# powerPCB9-2.net
KiCad netlist of a schematic drawn in Altium Designer
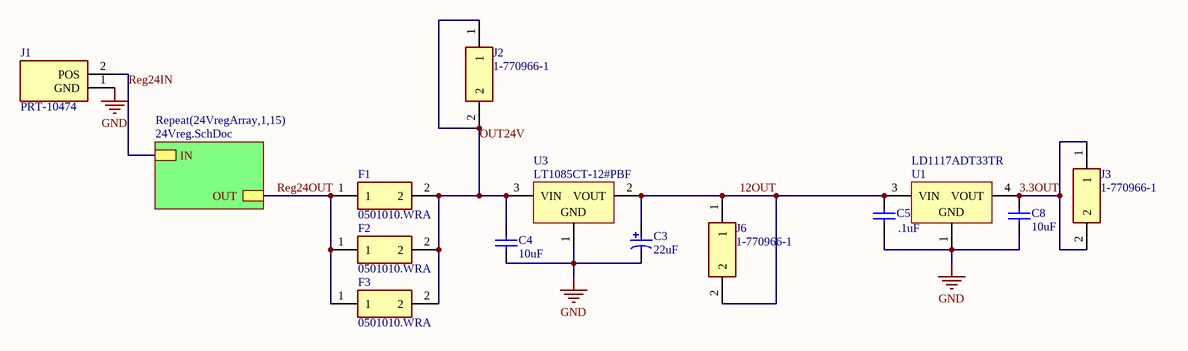
[diagram p0: powerPCB9-2.SchDoc]

(export (version "E")
  (design (tool "Eeschema 10.0.6"))
  (components
    (comp (ref "C3")
      (value "22uF")
      (footprint "KEMT-D-7343-31-2_L")
      (description "Capacitor, Tantalum, 22 uF, +/- 10%, 35 V, -55 to 125 degC, 2-Pin Molded, RoHS, Tape and Reel")
      (fields (field (name "VOLTAGE") "35VDC") (field (name "MANUFACTURER") "Kemet"))
      (libsource (lib "Altium Content Vault") (part "CAP-P-2"))
    )
    (comp (ref "C4")
      (value "10uF")
      (footprint "CAPC2013X135X45ML10T25")
      (fields (field (name "PART NUMBER") "GRM21BR61E106KA73L") (field (name "MANUFACTURER") "Murata"))
      (libsource (lib "Altium Content Vault") (part "CAP"))
    )
    (comp (ref "C5")
      (value ".1uF")
      (footprint "CAPC2013X135X45ML10T25")
      (description "Chip Capacitor, 0.1 uF, +/- 10%, 50 V, -55 to 125 degC, 0805 (2012 Metric), RoHS, Tape and Reel")
      (fields (field (name "VOLTAGE") "50V") (field (name "TOLERANCE") "10%"))
      (libsource (lib "Altium Content Vault") (part "CAP-NP-2"))
    )
    (comp (ref "C8")
      (value "10uF")
      (footprint "CAPC2013X135X45ML10T25")
      (fields (field (name "PART NUMBER") "GRM21BR61E106KA73L") (field (name "MANUFACTURER") "Murata"))
      (libsource (lib "Altium Content Vault") (part "CAP"))
    )
    (comp (ref "F1")
      (value "0501010.WRA")
      (footprint "SamacSys:FUSC3216X98N")
      (description "Fuse")
      (fields (field (name "MOUSER PART NUMBER") "576-0501010.WRA"))
      (libsource (lib "*") (part "0501010.WRA"))
    )
    (comp (ref "F2")
      (value "0501010.WRA")
      (footprint "SamacSys:FUSC3216X98N")
      (description "Fuse")
      (fields (field (name "MOUSER PART NUMBER") "576-0501010.WRA"))
      (libsource (lib "*") (part "0501010.WRA"))
    )
    (comp (ref "F3")
      (value "0501010.WRA")
      (footprint "SamacSys:FUSC3216X98N")
      (description "Fuse")
      (fields (field (name "MOUSER PART NUMBER") "576-0501010.WRA"))
      (libsource (lib "*") (part "0501010.WRA"))
    )
    (comp (ref "J1")
      (value "PRT-10474")
      (footprint "SamacSys:SHDR2W320P716_1X2_1574X813X1588P")
      (description "Connector")
      (fields (field (name "MOUSER PART NUMBER") "474-PRT-10474"))
      (libsource (lib "*") (part "PRT-10474"))
    )
    (comp (ref "J2")
      (value "1-770966-1")
      (footprint "SamacSys:17709661")
      (description "Connector")
      (fields (field (name "MOUSER PART NUMBER") "571-1-770966-1") (field (name "RS PART NUMBER") "7099906"))
      (libsource (lib "*") (part "1-770966-1"))
    )
    (comp (ref "J3")
      (value "1-770966-1")
      (footprint "SamacSys:17709661")
      (description "Connector")
      (fields (field (name "MOUSER PART NUMBER") "571-1-770966-1") (field (name "RS PART NUMBER") "7099906"))
      (libsource (lib "*") (part "1-770966-1"))
    )
    (comp (ref "J6")
      (value "1-770966-1")
      (footprint "SamacSys:17709661")
      (description "Connector")
      (fields (field (name "MOUSER PART NUMBER") "571-1-770966-1") (field (name "RS PART NUMBER") "7099906"))
      (libsource (lib "*") (part "1-770966-1"))
    )
    (comp (ref "U1")
      (value "LD1117ADT33TR")
      (footprint "TO-252_L")
      (description "1A, Low Drop Positive Voltage Regulator, 3.3V, 3-Pin DPAK, Tape and Reel")
      (libsource (lib "Altium Content Vault") (part "PM-REG-LD1117-SOT3"))
    )
    (comp (ref "U3")
      (value "LT1085CT-12#PBF")
      (footprint "LT-T-3")
      (fields (field (name "MANUFACTURER") "Linear Technology"))
      (libsource (lib "Altium Content Vault") (part "LT-LT1085-T-3"))
    )
  )
  (nets
    (net (code "1") (name "/3.3OUT") (class "Default")
      (node (ref "C8") (pin "2") (pinfunction "2_2") (pintype "passive"))
      (node (ref "J3") (pin "1") (pinfunction "1_1") (pintype "passive"))
      (node (ref "J3") (pin "2") (pinfunction "2_2") (pintype "passive"))
      (node (ref "U1") (pin "4") (pinfunction "VOUT_4") (pintype "power_in"))
    )
    (net (code "2") (name "/12OUT") (class "Default")
      (node (ref "C3") (pin "1") (pinfunction "1_1") (pintype "passive"))
      (node (ref "C5") (pin "2") (pinfunction "2_2") (pintype "passive"))
      (node (ref "J6") (pin "1") (pinfunction "1_1") (pintype "passive"))
      (node (ref "J6") (pin "2") (pinfunction "2_2") (pintype "passive"))
      (node (ref "U1") (pin "3") (pinfunction "VIN_3") (pintype "power_in"))
      (node (ref "U3") (pin "2") (pinfunction "VOUT_2") (pintype "power_in"))
    )
    (net (code "3") (name "/OUT24V") (class "Default")
      (node (ref "C4") (pin "2") (pinfunction "2_2") (pintype "passive"))
      (node (ref "F1") (pin "2") (pinfunction "2_2") (pintype "passive"))
      (node (ref "F2") (pin "2") (pinfunction "2_2") (pintype "passive"))
      (node (ref "F3") (pin "2") (pinfunction "2_2") (pintype "passive"))
      (node (ref "J2") (pin "1") (pinfunction "1_1") (pintype "passive"))
      (node (ref "J2") (pin "2") (pinfunction "2_2") (pintype "passive"))
      (node (ref "U3") (pin "3") (pinfunction "VIN_3") (pintype "power_in"))
    )
    (net (code "4") (name "/Reg24IN") (class "Default")
      (node (ref "J1") (pin "2") (pinfunction "POS_2") (pintype "power_in"))
    )
    (net (code "5") (name "/Reg24OUT") (class "Default")
      (node (ref "F1") (pin "1") (pinfunction "1_1") (pintype "passive"))
      (node (ref "F2") (pin "1") (pinfunction "1_1") (pintype "passive"))
      (node (ref "F3") (pin "1") (pinfunction "1_1") (pintype "passive"))
    )
    (net (code "6") (name "GND") (class "Default")
      (node (ref "C3") (pin "2") (pinfunction "2_2") (pintype "passive"))
      (node (ref "C4") (pin "1") (pinfunction "1_1") (pintype "passive"))
      (node (ref "C5") (pin "1") (pinfunction "1_1") (pintype "passive"))
      (node (ref "C8") (pin "1") (pinfunction "1_1") (pintype "passive"))
      (node (ref "J1") (pin "1") (pinfunction "GND_1") (pintype "power_in"))
      (node (ref "U1") (pin "1") (pinfunction "GND_1") (pintype "power_in"))
      (node (ref "U3") (pin "1") (pinfunction "GND_1") (pintype "power_in"))
    )
  )
)
